# whoop-v2_0-F3.net
KiCad netlist of a schematic drawn in EAGLE
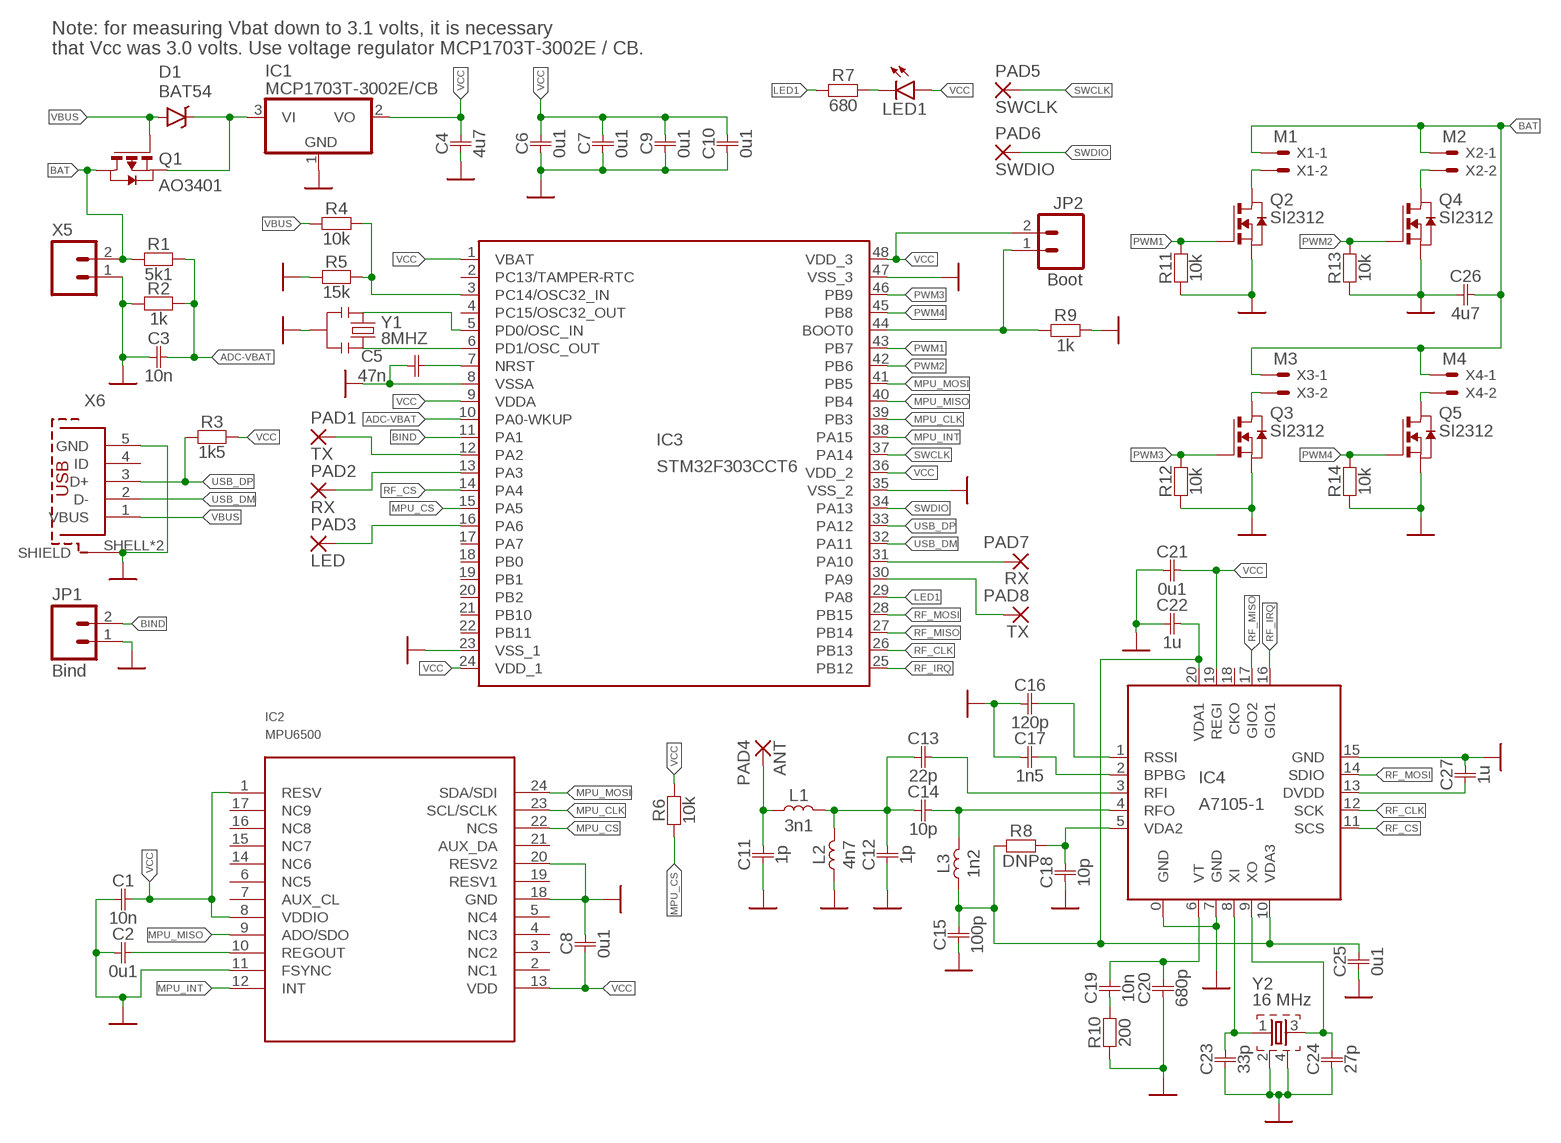
[diagram p0: schematic, sheet 1]

(export (version "E")
  (design (tool "Eeschema 10.0.6"))
  (components
    (comp (ref "C1")
      (value "10n")
      (footprint "eagle-import:0402")
      (libsource (lib "eagle-import") (part "C0402"))
    )
    (comp (ref "C2")
      (value "0u1")
      (footprint "eagle-import:0402")
      (libsource (lib "eagle-import") (part "C0402"))
    )
    (comp (ref "C3")
      (value "10n")
      (footprint "eagle-import:0402")
      (libsource (lib "eagle-import") (part "C0402"))
    )
    (comp (ref "C4")
      (value "4u7")
      (footprint "eagle-import:0805")
      (libsource (lib "eagle-import") (part "C0805"))
    )
    (comp (ref "C5")
      (value "47n")
      (footprint "eagle-import:0402")
      (libsource (lib "eagle-import") (part "C0402"))
    )
    (comp (ref "C6")
      (value "0u1")
      (footprint "eagle-import:0402")
      (libsource (lib "eagle-import") (part "C0402"))
    )
    (comp (ref "C7")
      (value "0u1")
      (footprint "eagle-import:0402")
      (libsource (lib "eagle-import") (part "C0402"))
    )
    (comp (ref "C8")
      (value "0u1")
      (footprint "eagle-import:0402")
      (libsource (lib "eagle-import") (part "C0402"))
    )
    (comp (ref "C9")
      (value "0u1")
      (footprint "eagle-import:0402")
      (libsource (lib "eagle-import") (part "C0402"))
    )
    (comp (ref "C10")
      (value "0u1")
      (footprint "eagle-import:0402")
      (libsource (lib "eagle-import") (part "C0402"))
    )
    (comp (ref "C11")
      (value "1p")
      (footprint "eagle-import:0402")
      (libsource (lib "eagle-import") (part "C0402"))
    )
    (comp (ref "C12")
      (value "1p")
      (footprint "eagle-import:0402")
      (libsource (lib "eagle-import") (part "C0402"))
    )
    (comp (ref "C13")
      (value "22p")
      (footprint "eagle-import:0402")
      (libsource (lib "eagle-import") (part "C0402"))
    )
    (comp (ref "C14")
      (value "10p")
      (footprint "eagle-import:0402")
      (libsource (lib "eagle-import") (part "C0402"))
    )
    (comp (ref "C15")
      (value "100p")
      (footprint "eagle-import:0402")
      (libsource (lib "eagle-import") (part "C0402"))
    )
    (comp (ref "C16")
      (value "120p")
      (footprint "eagle-import:0402")
      (libsource (lib "eagle-import") (part "C0402"))
    )
    (comp (ref "C17")
      (value "1n5")
      (footprint "eagle-import:0402")
      (libsource (lib "eagle-import") (part "C0402"))
    )
    (comp (ref "C18")
      (value "10p")
      (footprint "eagle-import:0402")
      (libsource (lib "eagle-import") (part "C0402"))
    )
    (comp (ref "C19")
      (value "10n")
      (footprint "eagle-import:0402")
      (libsource (lib "eagle-import") (part "C0402"))
    )
    (comp (ref "C20")
      (value "680p")
      (footprint "eagle-import:0402")
      (libsource (lib "eagle-import") (part "C0402"))
    )
    (comp (ref "C21")
      (value "0u1")
      (footprint "eagle-import:0402")
      (libsource (lib "eagle-import") (part "C0402"))
    )
    (comp (ref "C22")
      (value "1u")
      (footprint "eagle-import:0402")
      (libsource (lib "eagle-import") (part "C0402"))
    )
    (comp (ref "C23")
      (value "33p")
      (footprint "eagle-import:0402")
      (libsource (lib "eagle-import") (part "C0402"))
    )
    (comp (ref "C24")
      (value "27p")
      (footprint "eagle-import:0402")
      (libsource (lib "eagle-import") (part "C0402"))
    )
    (comp (ref "C25")
      (value "0u1")
      (footprint "eagle-import:0402")
      (libsource (lib "eagle-import") (part "C0402"))
    )
    (comp (ref "C26")
      (value "4u7")
      (footprint "eagle-import:0805")
      (libsource (lib "eagle-import") (part "C0805"))
    )
    (comp (ref "C27")
      (value "1u")
      (footprint "eagle-import:0402")
      (libsource (lib "eagle-import") (part "C0402"))
    )
    (comp (ref "D1")
      (value "BAT54")
      (footprint "eagle-import:SOD-323")
      (libsource (lib "eagle-import") (part "BAT20JFILM"))
    )
    (comp (ref "IC1")
      (value "MCP1703T-3002E/CB")
      (footprint "eagle-import:SOT23")
      (libsource (lib "eagle-import") (part "MCP1703CB"))
    )
    (comp (ref "IC2")
      (value "MPU6500")
      (footprint "eagle-import:LEAD-QFN24")
      (libsource (lib "eagle-import") (part "MPU-9250"))
    )
    (comp (ref "IC3")
      (value "STM32F303CCT6")
      (footprint "eagle-import:LQFP48")
      (libsource (lib "eagle-import") (part "STM32F103C8"))
    )
    (comp (ref "IC4")
      (value "A7105-1")
      (footprint "eagle-import:QFN20-1")
      (libsource (lib "eagle-import") (part "A7105-1"))
    )
    (comp (ref "JP1")
      (value "Bind")
      (footprint "eagle-import:1X02_1.27MM")
      (libsource (lib "eagle-import") (part "M021.27MM"))
    )
    (comp (ref "JP2")
      (value "Boot")
      (footprint "eagle-import:1X02_1.27MM")
      (libsource (lib "eagle-import") (part "M021.27MM"))
    )
    (comp (ref "L1")
      (value "3n1")
      (footprint "eagle-import:0402")
      (libsource (lib "eagle-import") (part "L0402"))
    )
    (comp (ref "L2")
      (value "4n7")
      (footprint "eagle-import:0402")
      (libsource (lib "eagle-import") (part "L0402"))
    )
    (comp (ref "L3")
      (value "1n2")
      (footprint "eagle-import:0402")
      (libsource (lib "eagle-import") (part "L0402"))
    )
    (comp (ref "LED1")
      (value "LED-RED0603")
      (footprint "eagle-import:LED-0603")
      (libsource (lib "eagle-import") (part "LED-RED0603"))
    )
    (comp (ref "PAD1")
      (value "TX")
      (footprint "eagle-import:SMD_R0,635")
      (libsource (lib "eagle-import") (part "SMD2SMD-R0,635"))
    )
    (comp (ref "PAD2")
      (value "RX")
      (footprint "eagle-import:1_0,6")
      (libsource (lib "eagle-import") (part "1/0,6"))
    )
    (comp (ref "PAD3")
      (value "LED")
      (footprint "eagle-import:1_0,6")
      (libsource (lib "eagle-import") (part "1/0,6"))
    )
    (comp (ref "PAD4")
      (value "ANT")
      (footprint "eagle-import:1_0,6")
      (libsource (lib "eagle-import") (part "1/0,6"))
    )
    (comp (ref "PAD5")
      (value "SWCLK")
      (footprint "eagle-import:SMD_R0,635")
      (libsource (lib "eagle-import") (part "SMD2SMD-R0,635"))
    )
    (comp (ref "PAD6")
      (value "SWDIO")
      (footprint "eagle-import:SMD_R0,635")
      (libsource (lib "eagle-import") (part "SMD2SMD-R0,635"))
    )
    (comp (ref "PAD7")
      (value "RX")
      (footprint "eagle-import:1_0,6")
      (libsource (lib "eagle-import") (part "1/0,6"))
    )
    (comp (ref "PAD8")
      (value "TX")
      (footprint "eagle-import:1_0,6")
      (libsource (lib "eagle-import") (part "1/0,6"))
    )
    (comp (ref "Q1")
      (value "AO3401")
      (footprint "eagle-import:SOT-23")
      (libsource (lib "eagle-import") (part "PMOSSOT23"))
    )
    (comp (ref "Q2")
      (value "SI2312")
      (footprint "eagle-import:SOT-23")
      (libsource (lib "eagle-import") (part "NMOSSOT23"))
    )
    (comp (ref "Q3")
      (value "SI2312")
      (footprint "eagle-import:SOT-23")
      (libsource (lib "eagle-import") (part "NMOSSOT23"))
    )
    (comp (ref "Q4")
      (value "SI2312")
      (footprint "eagle-import:SOT-23")
      (libsource (lib "eagle-import") (part "NMOSSOT23"))
    )
    (comp (ref "Q5")
      (value "SI2312")
      (footprint "eagle-import:SOT-23")
      (libsource (lib "eagle-import") (part "NMOSSOT23"))
    )
    (comp (ref "R1")
      (value "5k1")
      (footprint "eagle-import:0402")
      (libsource (lib "eagle-import") (part "R0402"))
    )
    (comp (ref "R2")
      (value "1k")
      (footprint "eagle-import:0402")
      (libsource (lib "eagle-import") (part "R0402"))
    )
    (comp (ref "R3")
      (value "1k5")
      (footprint "eagle-import:0402")
      (libsource (lib "eagle-import") (part "R0402"))
    )
    (comp (ref "R4")
      (value "10k")
      (footprint "eagle-import:0402")
      (libsource (lib "eagle-import") (part "R0402"))
    )
    (comp (ref "R5")
      (value "15k")
      (footprint "eagle-import:0402")
      (libsource (lib "eagle-import") (part "R0402"))
    )
    (comp (ref "R6")
      (value "10k")
      (footprint "eagle-import:0402")
      (libsource (lib "eagle-import") (part "R0402"))
    )
    (comp (ref "R7")
      (value "680")
      (footprint "eagle-import:0402")
      (libsource (lib "eagle-import") (part "R0402"))
    )
    (comp (ref "R8")
      (value "DNP")
      (footprint "eagle-import:0402")
      (libsource (lib "eagle-import") (part "R0402"))
    )
    (comp (ref "R9")
      (value "1k")
      (footprint "eagle-import:0402")
      (libsource (lib "eagle-import") (part "R0402"))
    )
    (comp (ref "R10")
      (value "200")
      (footprint "eagle-import:0402")
      (libsource (lib "eagle-import") (part "R0402"))
    )
    (comp (ref "R11")
      (value "10k")
      (footprint "eagle-import:0402")
      (libsource (lib "eagle-import") (part "R0402"))
    )
    (comp (ref "R12")
      (value "10k")
      (footprint "eagle-import:0402")
      (libsource (lib "eagle-import") (part "R0402"))
    )
    (comp (ref "R13")
      (value "10k")
      (footprint "eagle-import:0402")
      (libsource (lib "eagle-import") (part "R0402"))
    )
    (comp (ref "R14")
      (value "10k")
      (footprint "eagle-import:0402")
      (libsource (lib "eagle-import") (part "R0402"))
    )
    (comp (ref "X1")
      (value "M1")
      (footprint "eagle-import:53047-02")
      (fields (field (name "MF") "MOLEX") (field (name "MPN") "53047-0210"))
      (libsource (lib "eagle-import") (part "53?-02047"))
    )
    (comp (ref "X2")
      (value "M2")
      (footprint "eagle-import:53047-02")
      (fields (field (name "MF") "MOLEX") (field (name "MPN") "53047-0210"))
      (libsource (lib "eagle-import") (part "53?-02047"))
    )
    (comp (ref "X3")
      (value "M3")
      (footprint "eagle-import:53047-02")
      (fields (field (name "MF") "MOLEX") (field (name "MPN") "53047-0210"))
      (libsource (lib "eagle-import") (part "53?-02047"))
    )
    (comp (ref "X4")
      (value "M4")
      (footprint "eagle-import:53047-02")
      (fields (field (name "MF") "MOLEX") (field (name "MPN") "53047-0210"))
      (libsource (lib "eagle-import") (part "53?-02047"))
    )
    (comp (ref "X5")
      (value "M022MM")
      (footprint "eagle-import:1X02_2MM")
      (libsource (lib "eagle-import") (part "M022MM"))
    )
    (comp (ref "X6")
      (value "614105150721")
      (footprint "eagle-import:614105150721")
      (libsource (lib "eagle-import") (part "614105150721"))
    )
    (comp (ref "Y1")
      (value "8MHZ")
      (footprint "eagle-import:RESONATOR-SMD")
      (libsource (lib "eagle-import") (part "RESONATOR8MHZ"))
    )
    (comp (ref "Y2")
      (value "16 MHz")
      (footprint "eagle-import:FA-20H")
      (libsource (lib "eagle-import") (part "FA-3225"))
    )
  )
  (nets
    (net (code "1") (name "ADC-VBAT") (class "Default")
      (node (ref "C3") (pin "P$2") (pinfunction "P$2_P$2") (pintype "passive"))
      (node (ref "IC3") (pin "10") (pinfunction "PA0-WKUP_10") (pintype "bidirectional"))
      (node (ref "R1") (pin "P$1") (pinfunction "P$1_P$1") (pintype "passive"))
      (node (ref "R2") (pin "P$1") (pinfunction "P$1_P$1") (pintype "passive"))
    )
    (net (code "2") (name "BAT") (class "Default")
      (node (ref "C26") (pin "P$2") (pinfunction "P$2_P$2") (pintype "passive"))
      (node (ref "Q1") (pin "1") (pinfunction "D_1") (pintype "passive"))
      (node (ref "R1") (pin "P$2") (pinfunction "P$2_P$2") (pintype "passive"))
      (node (ref "X1") (pin "1") (pinfunction "S_1") (pintype "passive"))
      (node (ref "X2") (pin "1") (pinfunction "S_1") (pintype "passive"))
      (node (ref "X3") (pin "1") (pinfunction "S_1") (pintype "passive"))
      (node (ref "X4") (pin "1") (pinfunction "S_1") (pintype "passive"))
      (node (ref "X5") (pin "2") (pinfunction "2_2") (pintype "passive"))
    )
    (net (code "3") (name "BIND") (class "Default")
      (node (ref "IC3") (pin "11") (pinfunction "PA1_11") (pintype "bidirectional"))
      (node (ref "JP1") (pin "2") (pinfunction "2_2") (pintype "passive"))
    )
    (net (code "4") (name "GND") (class "Default")
      (node (ref "C1") (pin "P$1") (pinfunction "P$1_P$1") (pintype "passive"))
      (node (ref "C10") (pin "P$1") (pinfunction "P$1_P$1") (pintype "passive"))
      (node (ref "C11") (pin "P$1") (pinfunction "P$1_P$1") (pintype "passive"))
      (node (ref "C12") (pin "P$1") (pinfunction "P$1_P$1") (pintype "passive"))
      (node (ref "C15") (pin "P$1") (pinfunction "P$1_P$1") (pintype "passive"))
      (node (ref "C16") (pin "P$1") (pinfunction "P$1_P$1") (pintype "passive"))
      (node (ref "C17") (pin "P$1") (pinfunction "P$1_P$1") (pintype "passive"))
      (node (ref "C18") (pin "P$1") (pinfunction "P$1_P$1") (pintype "passive"))
      (node (ref "C2") (pin "P$1") (pinfunction "P$1_P$1") (pintype "passive"))
      (node (ref "C20") (pin "P$1") (pinfunction "P$1_P$1") (pintype "passive"))
      (node (ref "C21") (pin "P$1") (pinfunction "P$1_P$1") (pintype "passive"))
      (node (ref "C22") (pin "P$1") (pinfunction "P$1_P$1") (pintype "passive"))
      (node (ref "C23") (pin "P$1") (pinfunction "P$1_P$1") (pintype "passive"))
      (node (ref "C24") (pin "P$1") (pinfunction "P$1_P$1") (pintype "passive"))
      (node (ref "C25") (pin "P$1") (pinfunction "P$1_P$1") (pintype "passive"))
      (node (ref "C26") (pin "P$1") (pinfunction "P$1_P$1") (pintype "passive"))
      (node (ref "C27") (pin "P$2") (pinfunction "P$2_P$2") (pintype "passive"))
      (node (ref "C3") (pin "P$1") (pinfunction "P$1_P$1") (pintype "passive"))
      (node (ref "C4") (pin "P$1") (pinfunction "P$1_P$1") (pintype "passive"))
      (node (ref "C5") (pin "P$1") (pinfunction "P$1_P$1") (pintype "passive"))
      (node (ref "C6") (pin "P$1") (pinfunction "P$1_P$1") (pintype "passive"))
      (node (ref "C7") (pin "P$1") (pinfunction "P$1_P$1") (pintype "passive"))
      (node (ref "C8") (pin "P$2") (pinfunction "P$2_P$2") (pintype "passive"))
      (node (ref "C9") (pin "P$1") (pinfunction "P$1_P$1") (pintype "passive"))
      (node (ref "IC1") (pin "1") (pinfunction "GND_1") (pintype "passive"))
      (node (ref "IC2") (pin "11") (pinfunction "FSYNC_11") (pintype "bidirectional"))
      (node (ref "IC2") (pin "18") (pinfunction "GND_18") (pintype "bidirectional"))
      (node (ref "IC2") (pin "20") (pinfunction "RESV2_20") (pintype "bidirectional"))
      (node (ref "IC3") (pin "23") (pinfunction "VSS_1_23") (pintype "power_in"))
      (node (ref "IC3") (pin "35") (pinfunction "VSS_2_35") (pintype "power_in"))
      (node (ref "IC3") (pin "47") (pinfunction "VSS_3_47") (pintype "power_in"))
      (node (ref "IC3") (pin "8") (pinfunction "VSSA_8") (pintype "power_in"))
      (node (ref "IC4") (pin "0") (pinfunction "GND_0") (pintype "power_in"))
      (node (ref "IC4") (pin "15") (pinfunction "GND_15") (pintype "power_in"))
      (node (ref "IC4") (pin "7") (pinfunction "GND_7") (pintype "power_in"))
      (node (ref "JP1") (pin "1") (pinfunction "1_1") (pintype "passive"))
      (node (ref "L2") (pin "P$1") (pinfunction "P$1_P$1") (pintype "passive"))
      (node (ref "Q2") (pin "2") (pinfunction "S_2") (pintype "passive"))
      (node (ref "Q3") (pin "2") (pinfunction "S_2") (pintype "passive"))
      (node (ref "Q4") (pin "2") (pinfunction "S_2") (pintype "passive"))
      (node (ref "Q5") (pin "2") (pinfunction "S_2") (pintype "passive"))
      (node (ref "R10") (pin "P$1") (pinfunction "P$1_P$1") (pintype "passive"))
      (node (ref "R11") (pin "P$1") (pinfunction "P$1_P$1") (pintype "passive"))
      (node (ref "R12") (pin "P$1") (pinfunction "P$1_P$1") (pintype "passive"))
      (node (ref "R13") (pin "P$1") (pinfunction "P$1_P$1") (pintype "passive"))
      (node (ref "R14") (pin "P$1") (pinfunction "P$1_P$1") (pintype "passive"))
      (node (ref "R2") (pin "P$2") (pinfunction "P$2_P$2") (pintype "passive"))
      (node (ref "R5") (pin "P$2") (pinfunction "P$2_P$2") (pintype "passive"))
      (node (ref "R9") (pin "P$2") (pinfunction "P$2_P$2") (pintype "passive"))
      (node (ref "X5") (pin "1") (pinfunction "1_1") (pintype "passive"))
      (node (ref "X6") (pin "5") (pinfunction "GND_5") (pintype "passive"))
      (node (ref "X6") (pin "SHELL") (pinfunction "SHIELD_SHELL") (pintype "passive"))
      (node (ref "X6") (pin "SHELL1") (pinfunction "SHIELD_SHELL1") (pintype "passive"))
      (node (ref "Y1") (pin "2") (pinfunction "2_2") (pintype "passive"))
      (node (ref "Y2") (pin "2") (pinfunction "2_2") (pintype "passive"))
      (node (ref "Y2") (pin "4") (pinfunction "4_4") (pintype "passive"))
    )
    (net (code "5") (name "LED1") (class "Default")
      (node (ref "IC3") (pin "29") (pinfunction "PA8_29") (pintype "bidirectional"))
      (node (ref "R7") (pin "P$1") (pinfunction "P$1_P$1") (pintype "passive"))
    )
    (net (code "6") (name "MPU_CLK") (class "Default")
      (node (ref "IC2") (pin "23") (pinfunction "SCL/SCLK_23") (pintype "bidirectional"))
      (node (ref "IC3") (pin "39") (pinfunction "PB3_39") (pintype "bidirectional"))
    )
    (net (code "7") (name "MPU_CS") (class "Default")
      (node (ref "IC2") (pin "22") (pinfunction "NCS_22") (pintype "bidirectional"))
      (node (ref "IC3") (pin "15") (pinfunction "PA5_15") (pintype "bidirectional"))
      (node (ref "R6") (pin "P$1") (pinfunction "P$1_P$1") (pintype "passive"))
    )
    (net (code "8") (name "MPU_INT") (class "Default")
      (node (ref "IC2") (pin "12") (pinfunction "INT_12") (pintype "bidirectional"))
      (node (ref "IC3") (pin "38") (pinfunction "PA15_38") (pintype "bidirectional"))
    )
    (net (code "9") (name "MPU_MISO") (class "Default")
      (node (ref "IC2") (pin "9") (pinfunction "ADO/SDO_9") (pintype "bidirectional"))
      (node (ref "IC3") (pin "40") (pinfunction "PB4_40") (pintype "bidirectional"))
    )
    (net (code "10") (name "MPU_MOSI") (class "Default")
      (node (ref "IC2") (pin "24") (pinfunction "SDA/SDI_24") (pintype "bidirectional"))
      (node (ref "IC3") (pin "41") (pinfunction "PB5_41") (pintype "bidirectional"))
    )
    (net (code "11") (name "Net-(C12-PadP$2)") (class "Default")
      (node (ref "C12") (pin "P$2") (pinfunction "P$2_P$2") (pintype "passive"))
      (node (ref "C13") (pin "P$1") (pinfunction "P$1_P$1") (pintype "passive"))
      (node (ref "C14") (pin "P$1") (pinfunction "P$1_P$1") (pintype "passive"))
      (node (ref "L1") (pin "P$2") (pinfunction "P$2_P$2") (pintype "passive"))
      (node (ref "L2") (pin "P$2") (pinfunction "P$2_P$2") (pintype "passive"))
    )
    (net (code "12") (name "Net-(C19-PadP$1)") (class "Default")
      (node (ref "C19") (pin "P$1") (pinfunction "P$1_P$1") (pintype "passive"))
      (node (ref "R10") (pin "P$2") (pinfunction "P$2_P$2") (pintype "passive"))
    )
    (net (code "13") (name "Net-(IC1-VI)") (class "Default")
      (node (ref "D1") (pin "C") (pinfunction "C_C") (pintype "passive"))
      (node (ref "IC1") (pin "3") (pinfunction "VI_3") (pintype "input"))
      (node (ref "Q1") (pin "2") (pinfunction "S_2") (pintype "passive"))
    )
    (net (code "14") (name "Net-(IC2-REGOUT)") (class "Default")
      (node (ref "C2") (pin "P$2") (pinfunction "P$2_P$2") (pintype "passive"))
      (node (ref "IC2") (pin "10") (pinfunction "REGOUT_10") (pintype "bidirectional"))
    )
    (net (code "15") (name "Net-(IC3-BOOT0)") (class "Default")
      (node (ref "IC3") (pin "44") (pinfunction "BOOT0_44") (pintype "input"))
      (node (ref "JP2") (pin "1") (pinfunction "1_1") (pintype "passive"))
      (node (ref "R9") (pin "P$1") (pinfunction "P$1_P$1") (pintype "passive"))
    )
    (net (code "16") (name "Net-(IC3-NRST)") (class "Default")
      (node (ref "C5") (pin "P$2") (pinfunction "P$2_P$2") (pintype "passive"))
      (node (ref "IC3") (pin "7") (pinfunction "NRST_7") (pintype "input"))
    )
    (net (code "17") (name "Net-(IC3-PA2)") (class "Default")
      (node (ref "IC3") (pin "12") (pinfunction "PA2_12") (pintype "bidirectional"))
      (node (ref "PAD1") (pin "1") (pinfunction "P_1") (pintype "passive"))
    )
    (net (code "18") (name "Net-(IC3-PA3)") (class "Default")
      (node (ref "IC3") (pin "13") (pinfunction "PA3_13") (pintype "bidirectional"))
      (node (ref "PAD2") (pin "1") (pinfunction "P_1") (pintype "passive"))
    )
    (net (code "19") (name "Net-(IC3-PA6)") (class "Default")
      (node (ref "IC3") (pin "16") (pinfunction "PA6_16") (pintype "bidirectional"))
      (node (ref "PAD3") (pin "1") (pinfunction "P_1") (pintype "passive"))
    )
    (net (code "20") (name "Net-(IC3-PA9)") (class "Default")
      (node (ref "IC3") (pin "30") (pinfunction "PA9_30") (pintype "bidirectional"))
      (node (ref "PAD8") (pin "1") (pinfunction "P_1") (pintype "passive"))
    )
    (net (code "21") (name "Net-(IC3-PA10)") (class "Default")
      (node (ref "IC3") (pin "31") (pinfunction "PA10_31") (pintype "bidirectional"))
      (node (ref "PAD7") (pin "1") (pinfunction "P_1") (pintype "passive"))
    )
    (net (code "22") (name "Net-(IC3-PC14{slash}OSC32_IN)") (class "Default")
      (node (ref "IC3") (pin "3") (pinfunction "PC14/OSC32_IN_3") (pintype "bidirectional"))
      (node (ref "R4") (pin "P$2") (pinfunction "P$2_P$2") (pintype "passive"))
      (node (ref "R5") (pin "P$1") (pinfunction "P$1_P$1") (pintype "passive"))
    )
    (net (code "23") (name "Net-(IC3-PD0{slash}OSC_IN)") (class "Default")
      (node (ref "IC3") (pin "5") (pinfunction "PD0/OSC_IN_5") (pintype "bidirectional"))
      (node (ref "Y1") (pin "1") (pinfunction "1_1") (pintype "passive"))
    )
    (net (code "24") (name "Net-(IC3-PD1{slash}OSC_OUT)") (class "Default")
      (node (ref "IC3") (pin "6") (pinfunction "PD1/OSC_OUT_6") (pintype "bidirectional"))
      (node (ref "Y1") (pin "3") (pinfunction "3_3") (pintype "passive"))
    )
    (net (code "25") (name "Net-(IC4-BPBG)") (class "Default")
      (node (ref "C17") (pin "P$2") (pinfunction "P$2_P$2") (pintype "passive"))
      (node (ref "IC4") (pin "2") (pinfunction "BPBG_2") (pintype "output"))
    )
    (net (code "26") (name "Net-(IC4-DVDD)") (class "Default")
      (node (ref "C27") (pin "P$1") (pinfunction "P$1_P$1") (pintype "passive"))
      (node (ref "IC4") (pin "13") (pinfunction "DVDD_13") (pintype "input"))
    )
    (net (code "27") (name "Net-(IC4-RFI)") (class "Default")
      (node (ref "C13") (pin "P$2") (pinfunction "P$2_P$2") (pintype "passive"))
      (node (ref "IC4") (pin "3") (pinfunction "RFI_3") (pintype "input"))
    )
    (net (code "28") (name "Net-(IC4-RFO)") (class "Default")
      (node (ref "C14") (pin "P$2") (pinfunction "P$2_P$2") (pintype "passive"))
      (node (ref "IC4") (pin "4") (pinfunction "RFO_4") (pintype "output"))
      (node (ref "L3") (pin "P$1") (pinfunction "P$1_P$1") (pintype "passive"))
    )
    (net (code "29") (name "Net-(IC4-RSSI)") (class "Default")
      (node (ref "C16") (pin "P$2") (pinfunction "P$2_P$2") (pintype "passive"))
      (node (ref "IC4") (pin "1") (pinfunction "RSSI_1") (pintype "output"))
    )
    (net (code "30") (name "Net-(IC4-VDA1)") (class "Default")
      (node (ref "C15") (pin "P$2") (pinfunction "P$2_P$2") (pintype "passive"))
      (node (ref "C22") (pin "P$2") (pinfunction "P$2_P$2") (pintype "passive"))
      (node (ref "C25") (pin "P$2") (pinfunction "P$2_P$2") (pintype "passive"))
      (node (ref "IC4") (pin "10") (pinfunction "VDA3_10") (pintype "input"))
      (node (ref "IC4") (pin "20") (pinfunction "VDA1_20") (pintype "bidirectional"))
      (node (ref "L3") (pin "P$2") (pinfunction "P$2_P$2") (pintype "passive"))
      (node (ref "R8") (pin "P$1") (pinfunction "P$1_P$1") (pintype "passive"))
    )
    (net (code "31") (name "Net-(IC4-VDA2)") (class "Default")
      (node (ref "C18") (pin "P$2") (pinfunction "P$2_P$2") (pintype "passive"))
      (node (ref "IC4") (pin "5") (pinfunction "VDA2_5") (pintype "bidirectional"))
      (node (ref "R8") (pin "P$2") (pinfunction "P$2_P$2") (pintype "passive"))
    )
    (net (code "32") (name "Net-(IC4-VT)") (class "Default")
      (node (ref "C19") (pin "P$2") (pinfunction "P$2_P$2") (pintype "passive"))
      (node (ref "C20") (pin "P$2") (pinfunction "P$2_P$2") (pintype "passive"))
      (node (ref "IC4") (pin "6") (pinfunction "VT_6") (pintype "input"))
    )
    (net (code "33") (name "Net-(IC4-XI)") (class "Default")
      (node (ref "C23") (pin "P$2") (pinfunction "P$2_P$2") (pintype "passive"))
      (node (ref "IC4") (pin "8") (pinfunction "XI_8") (pintype "input"))
      (node (ref "Y2") (pin "1") (pinfunction "1_1") (pintype "passive"))
    )
    (net (code "34") (name "Net-(IC4-XO)") (class "Default")
      (node (ref "C24") (pin "P$2") (pinfunction "P$2_P$2") (pintype "passive"))
      (node (ref "IC4") (pin "9") (pinfunction "XO_9") (pintype "output"))
      (node (ref "Y2") (pin "3") (pinfunction "3_3") (pintype "passive"))
    )
    (net (code "35") (name "Net-(LED1-PadC)") (class "Default")
      (node (ref "LED1") (pin "C") (pinfunction "C_C") (pintype "passive"))
      (node (ref "R7") (pin "P$2") (pinfunction "P$2_P$2") (pintype "passive"))
    )
    (net (code "36") (name "Net-(PAD4-P)") (class "Default")
      (node (ref "C11") (pin "P$2") (pinfunction "P$2_P$2") (pintype "passive"))
      (node (ref "L1") (pin "P$1") (pinfunction "P$1_P$1") (pintype "passive"))
      (node (ref "PAD4") (pin "1") (pinfunction "P_1") (pintype "passive"))
    )
    (net (code "37") (name "Net-(Q2-D)") (class "Default")
      (node (ref "Q2") (pin "1") (pinfunction "D_1") (pintype "passive"))
      (node (ref "X1") (pin "2") (pinfunction "S_2") (pintype "passive"))
    )
    (net (code "38") (name "Net-(Q3-D)") (class "Default")
      (node (ref "Q3") (pin "1") (pinfunction "D_1") (pintype "passive"))
      (node (ref "X3") (pin "2") (pinfunction "S_2") (pintype "passive"))
    )
    (net (code "39") (name "Net-(Q4-D)") (class "Default")
      (node (ref "Q4") (pin "1") (pinfunction "D_1") (pintype "passive"))
      (node (ref "X2") (pin "2") (pinfunction "S_2") (pintype "passive"))
    )
    (net (code "40") (name "Net-(Q5-D)") (class "Default")
      (node (ref "Q5") (pin "1") (pinfunction "D_1") (pintype "passive"))
      (node (ref "X4") (pin "2") (pinfunction "S_2") (pintype "passive"))
    )
    (net (code "41") (name "PWM1") (class "Default")
      (node (ref "IC3") (pin "43") (pinfunction "PB7_43") (pintype "bidirectional"))
      (node (ref "Q2") (pin "3") (pinfunction "G_3") (pintype "passive"))
      (node (ref "R11") (pin "P$2") (pinfunction "P$2_P$2") (pintype "passive"))
    )
    (net (code "42") (name "PWM2") (class "Default")
      (node (ref "IC3") (pin "42") (pinfunction "PB6_42") (pintype "bidirectional"))
      (node (ref "Q4") (pin "3") (pinfunction "G_3") (pintype "passive"))
      (node (ref "R13") (pin "P$2") (pinfunction "P$2_P$2") (pintype "passive"))
    )
    (net (code "43") (name "PWM3") (class "Default")
      (node (ref "IC3") (pin "46") (pinfunction "PB9_46") (pintype "bidirectional"))
      (node (ref "Q3") (pin "3") (pinfunction "G_3") (pintype "passive"))
      (node (ref "R12") (pin "P$2") (pinfunction "P$2_P$2") (pintype "passive"))
    )
    (net (code "44") (name "PWM4") (class "Default")
      (node (ref "IC3") (pin "45") (pinfunction "PB8_45") (pintype "bidirectional"))
      (node (ref "Q5") (pin "3") (pinfunction "G_3") (pintype "passive"))
      (node (ref "R14") (pin "P$2") (pinfunction "P$2_P$2") (pintype "passive"))
    )
    (net (code "45") (name "RF_CLK") (class "Default")
      (node (ref "IC3") (pin "26") (pinfunction "PB13_26") (pintype "bidirectional"))
      (node (ref "IC4") (pin "12") (pinfunction "SCK_12") (pintype "input"))
    )
    (net (code "46") (name "RF_CS") (class "Default")
      (node (ref "IC3") (pin "14") (pinfunction "PA4_14") (pintype "bidirectional"))
      (node (ref "IC4") (pin "11") (pinfunction "SCS_11") (pintype "input"))
    )
    (net (code "47") (name "RF_IRQ") (class "Default")
      (node (ref "IC3") (pin "25") (pinfunction "PB12_25") (pintype "bidirectional"))
      (node (ref "IC4") (pin "16") (pinfunction "GIO1_16") (pintype "bidirectional"))
    )
    (net (code "48") (name "RF_MISO") (class "Default")
      (node (ref "IC3") (pin "27") (pinfunction "PB14_27") (pintype "bidirectional"))
      (node (ref "IC4") (pin "17") (pinfunction "GIO2_17") (pintype "bidirectional"))
    )
    (net (code "49") (name "RF_MOSI") (class "Default")
      (node (ref "IC3") (pin "28") (pinfunction "PB15_28") (pintype "bidirectional"))
      (node (ref "IC4") (pin "14") (pinfunction "SDIO_14") (pintype "bidirectional"))
    )
    (net (code "50") (name "SWCLK") (class "Default")
      (node (ref "IC3") (pin "37") (pinfunction "PA14_37") (pintype "bidirectional"))
      (node (ref "PAD5") (pin "1") (pinfunction "P_1") (pintype "passive"))
    )
    (net (code "51") (name "SWDIO") (class "Default")
      (node (ref "IC3") (pin "34") (pinfunction "PA13_34") (pintype "bidirectional"))
      (node (ref "PAD6") (pin "1") (pinfunction "P_1") (pintype "passive"))
    )
    (net (code "52") (name "USB_DM") (class "Default")
      (node (ref "IC3") (pin "32") (pinfunction "PA11_32") (pintype "bidirectional"))
      (node (ref "X6") (pin "2") (pinfunction "D-_2") (pintype "passive"))
    )
    (net (code "53") (name "USB_DP") (class "Default")
      (node (ref "IC3") (pin "33") (pinfunction "PA12_33") (pintype "bidirectional"))
      (node (ref "R3") (pin "P$2") (pinfunction "P$2_P$2") (pintype "passive"))
      (node (ref "X6") (pin "3") (pinfunction "D+_3") (pintype "passive"))
    )
    (net (code "54") (name "VBUS") (class "Default")
      (node (ref "D1") (pin "A") (pinfunction "A_A") (pintype "passive"))
      (node (ref "Q1") (pin "3") (pinfunction "G_3") (pintype "passive"))
      (node (ref "R4") (pin "P$1") (pinfunction "P$1_P$1") (pintype "passive"))
      (node (ref "X6") (pin "1") (pinfunction "VBUS_1") (pintype "passive"))
    )
    (net (code "55") (name "VCC") (class "Default")
      (node (ref "C1") (pin "P$2") (pinfunction "P$2_P$2") (pintype "passive"))
      (node (ref "C10") (pin "P$2") (pinfunction "P$2_P$2") (pintype "passive"))
      (node (ref "C21") (pin "P$2") (pinfunction "P$2_P$2") (pintype "passive"))
      (node (ref "C4") (pin "P$2") (pinfunction "P$2_P$2") (pintype "passive"))
      (node (ref "C6") (pin "P$2") (pinfunction "P$2_P$2") (pintype "passive"))
      (node (ref "C7") (pin "P$2") (pinfunction "P$2_P$2") (pintype "passive"))
      (node (ref "C8") (pin "P$1") (pinfunction "P$1_P$1") (pintype "passive"))
      (node (ref "C9") (pin "P$2") (pinfunction "P$2_P$2") (pintype "passive"))
      (node (ref "IC1") (pin "2") (pinfunction "VO_2") (pintype "passive"))
      (node (ref "IC2") (pin "1") (pinfunction "RESV_1") (pintype "bidirectional"))
      (node (ref "IC2") (pin "13") (pinfunction "VDD_13") (pintype "bidirectional"))
      (node (ref "IC2") (pin "8") (pinfunction "VDDIO_8") (pintype "bidirectional"))
      (node (ref "IC3") (pin "1") (pinfunction "VBAT_1") (pintype "power_in"))
      (node (ref "IC3") (pin "24") (pinfunction "VDD_1_24") (pintype "power_in"))
      (node (ref "IC3") (pin "36") (pinfunction "VDD_2_36") (pintype "power_in"))
      (node (ref "IC3") (pin "48") (pinfunction "VDD_3_48") (pintype "power_in"))
      (node (ref "IC3") (pin "9") (pinfunction "VDDA_9") (pintype "power_in"))
      (node (ref "IC4") (pin "19") (pinfunction "REGI_19") (pintype "power_in"))
      (node (ref "JP2") (pin "2") (pinfunction "2_2") (pintype "passive"))
      (node (ref "LED1") (pin "A") (pinfunction "A_A") (pintype "passive"))
      (node (ref "R3") (pin "P$1") (pinfunction "P$1_P$1") (pintype "passive"))
      (node (ref "R6") (pin "P$2") (pinfunction "P$2_P$2") (pintype "passive"))
    )
    (net (code "56") (name "unconnected-(IC2-AUX_CL-Pad7)") (class "Default")
      (node (ref "IC2") (pin "7") (pinfunction "AUX_CL_7") (pintype "bidirectional"))
    )
    (net (code "57") (name "unconnected-(IC2-AUX_DA-Pad21)") (class "Default")
      (node (ref "IC2") (pin "21") (pinfunction "AUX_DA_21") (pintype "bidirectional"))
    )
    (net (code "58") (name "unconnected-(IC2-NC1-Pad2)") (class "Default")
      (node (ref "IC2") (pin "2") (pinfunction "NC1_2") (pintype "bidirectional"))
    )
    (net (code "59") (name "unconnected-(IC2-NC2-Pad3)") (class "Default")
      (node (ref "IC2") (pin "3") (pinfunction "NC2_3") (pintype "bidirectional"))
    )
    (net (code "60") (name "unconnected-(IC2-NC3-Pad4)") (class "Default")
      (node (ref "IC2") (pin "4") (pinfunction "NC3_4") (pintype "bidirectional"))
    )
    (net (code "61") (name "unconnected-(IC2-NC4-Pad5)") (class "Default")
      (node (ref "IC2") (pin "5") (pinfunction "NC4_5") (pintype "bidirectional"))
    )
    (net (code "62") (name "unconnected-(IC2-NC5-Pad6)") (class "Default")
      (node (ref "IC2") (pin "6") (pinfunction "NC5_6") (pintype "bidirectional"))
    )
    (net (code "63") (name "unconnected-(IC2-NC6-Pad14)") (class "Default")
      (node (ref "IC2") (pin "14") (pinfunction "NC6_14") (pintype "bidirectional"))
    )
    (net (code "64") (name "unconnected-(IC2-NC7-Pad15)") (class "Default")
      (node (ref "IC2") (pin "15") (pinfunction "NC7_15") (pintype "bidirectional"))
    )
    (net (code "65") (name "unconnected-(IC2-NC8-Pad16)") (class "Default")
      (node (ref "IC2") (pin "16") (pinfunction "NC8_16") (pintype "bidirectional"))
    )
    (net (code "66") (name "unconnected-(IC2-NC9-Pad17)") (class "Default")
      (node (ref "IC2") (pin "17") (pinfunction "NC9_17") (pintype "bidirectional"))
    )
    (net (code "67") (name "unconnected-(IC2-RESV1-Pad19)") (class "Default")
      (node (ref "IC2") (pin "19") (pinfunction "RESV1_19") (pintype "bidirectional"))
    )
    (net (code "68") (name "unconnected-(IC3-PA7-Pad17)") (class "Default")
      (node (ref "IC3") (pin "17") (pinfunction "PA7_17") (pintype "bidirectional"))
    )
    (net (code "69") (name "unconnected-(IC3-PB0-Pad18)") (class "Default")
      (node (ref "IC3") (pin "18") (pinfunction "PB0_18") (pintype "bidirectional"))
    )
    (net (code "70") (name "unconnected-(IC3-PB1-Pad19)") (class "Default")
      (node (ref "IC3") (pin "19") (pinfunction "PB1_19") (pintype "bidirectional"))
    )
    (net (code "71") (name "unconnected-(IC3-PB2-Pad20)") (class "Default")
      (node (ref "IC3") (pin "20") (pinfunction "PB2_20") (pintype "bidirectional"))
    )
    (net (code "72") (name "unconnected-(IC3-PB10-Pad21)") (class "Default")
      (node (ref "IC3") (pin "21") (pinfunction "PB10_21") (pintype "bidirectional"))
    )
    (net (code "73") (name "unconnected-(IC3-PB11-Pad22)") (class "Default")
      (node (ref "IC3") (pin "22") (pinfunction "PB11_22") (pintype "bidirectional"))
    )
    (net (code "74") (name "unconnected-(IC3-PC13{slash}TAMPER-RTC-Pad2)") (class "Default")
      (node (ref "IC3") (pin "2") (pinfunction "PC13/TAMPER-RTC_2") (pintype "bidirectional"))
    )
    (net (code "75") (name "unconnected-(IC3-PC15{slash}OSC32_OUT-Pad4)") (class "Default")
      (node (ref "IC3") (pin "4") (pinfunction "PC15/OSC32_OUT_4") (pintype "bidirectional"))
    )
    (net (code "76") (name "unconnected-(IC4-CKO-Pad18)") (class "Default")
      (node (ref "IC4") (pin "18") (pinfunction "CKO_18") (pintype "output"))
    )
    (net (code "77") (name "unconnected-(X6-ID-Pad4)") (class "Default")
      (node (ref "X6") (pin "4") (pinfunction "ID_4") (pintype "passive"))
    )
  )
)
